# arduino_voltage_monitor_shield.net
KiCad netlist of a schematic drawn in Altium Designer
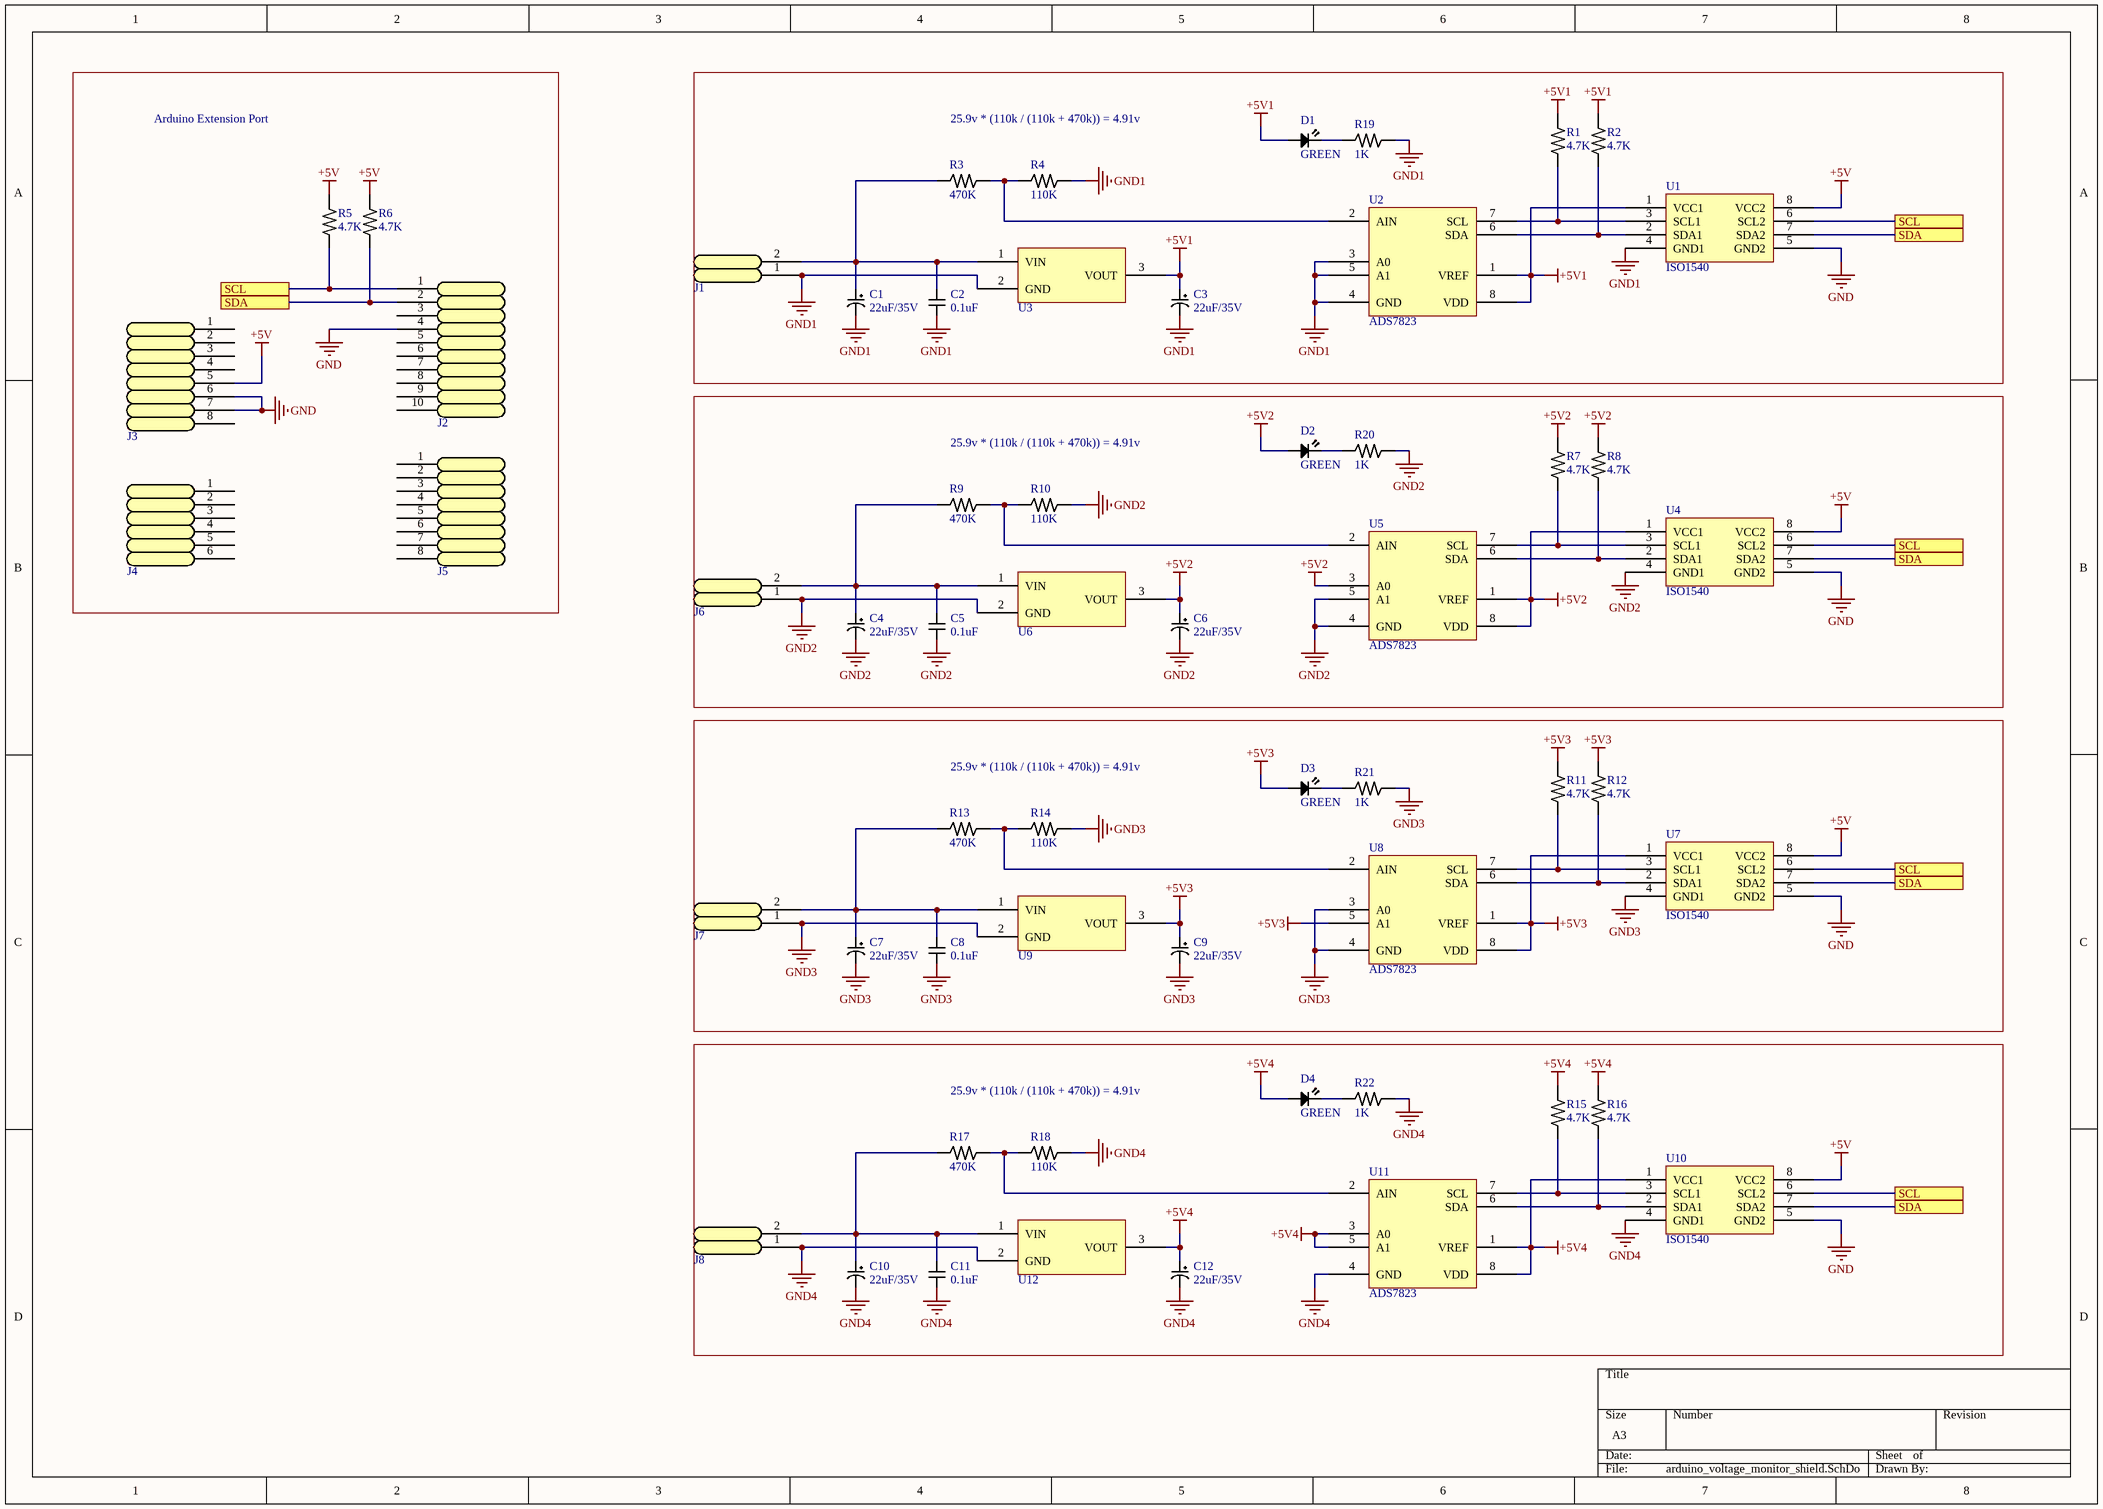
[diagram p0: arduino_voltage_monitor_shield.SchDoc]

(export (version "E")
  (design (tool "Eeschema 10.0.6"))
  (components
    (comp (ref "C1")
      (value "22uF/35V")
      (footprint "ECAP-TANTAL-A")
      (description "Polarized Capacitor")
      (fields (field (name "Comment") "EC"))
      (libsource (lib "arduino_voltage_monitor_shield") (part "EC"))
    )
    (comp (ref "C2")
      (value "0.1uF")
      (footprint "CAP1608L")
      (description "Non-polarized Capacitor")
      (fields (field (name "Comment") "C"))
      (libsource (lib "arduino_voltage_monitor_shield") (part "C"))
    )
    (comp (ref "C3")
      (value "22uF/35V")
      (footprint "ECAP-TANTAL-A")
      (description "Polarized Capacitor")
      (fields (field (name "Comment") "EC"))
      (libsource (lib "arduino_voltage_monitor_shield") (part "EC"))
    )
    (comp (ref "C4")
      (value "22uF/35V")
      (footprint "ECAP-TANTAL-A")
      (description "Polarized Capacitor")
      (fields (field (name "Comment") "EC"))
      (libsource (lib "arduino_voltage_monitor_shield") (part "EC"))
    )
    (comp (ref "C5")
      (value "0.1uF")
      (footprint "CAP1608L")
      (description "Non-polarized Capacitor")
      (fields (field (name "Comment") "C"))
      (libsource (lib "arduino_voltage_monitor_shield") (part "C"))
    )
    (comp (ref "C6")
      (value "22uF/35V")
      (footprint "ECAP-TANTAL-A")
      (description "Polarized Capacitor")
      (fields (field (name "Comment") "EC"))
      (libsource (lib "arduino_voltage_monitor_shield") (part "EC"))
    )
    (comp (ref "C7")
      (value "22uF/35V")
      (footprint "ECAP-TANTAL-A")
      (description "Polarized Capacitor")
      (fields (field (name "Comment") "EC"))
      (libsource (lib "arduino_voltage_monitor_shield") (part "EC"))
    )
    (comp (ref "C8")
      (value "0.1uF")
      (footprint "CAP1608L")
      (description "Non-polarized Capacitor")
      (fields (field (name "Comment") "C"))
      (libsource (lib "arduino_voltage_monitor_shield") (part "C"))
    )
    (comp (ref "C9")
      (value "22uF/35V")
      (footprint "ECAP-TANTAL-A")
      (description "Polarized Capacitor")
      (fields (field (name "Comment") "EC"))
      (libsource (lib "arduino_voltage_monitor_shield") (part "EC"))
    )
    (comp (ref "C10")
      (value "22uF/35V")
      (footprint "ECAP-TANTAL-A")
      (description "Polarized Capacitor")
      (fields (field (name "Comment") "EC"))
      (libsource (lib "arduino_voltage_monitor_shield") (part "EC"))
    )
    (comp (ref "C11")
      (value "0.1uF")
      (footprint "CAP1608L")
      (description "Non-polarized Capacitor")
      (fields (field (name "Comment") "C"))
      (libsource (lib "arduino_voltage_monitor_shield") (part "C"))
    )
    (comp (ref "C12")
      (value "22uF/35V")
      (footprint "ECAP-TANTAL-A")
      (description "Polarized Capacitor")
      (fields (field (name "Comment") "EC"))
      (libsource (lib "arduino_voltage_monitor_shield") (part "EC"))
    )
    (comp (ref "D1")
      (value "GREEN")
      (footprint "LED1608L")
      (description "Typical LED")
      (fields (field (name "Comment") "LED"))
      (libsource (lib "arduino_voltage_monitor_shield") (part "LED"))
    )
    (comp (ref "D2")
      (value "GREEN")
      (footprint "LED1608L")
      (description "Typical LED")
      (fields (field (name "Comment") "LED"))
      (libsource (lib "arduino_voltage_monitor_shield") (part "LED"))
    )
    (comp (ref "D3")
      (value "GREEN")
      (footprint "LED1608L")
      (description "Typical LED")
      (fields (field (name "Comment") "LED"))
      (libsource (lib "arduino_voltage_monitor_shield") (part "LED"))
    )
    (comp (ref "D4")
      (value "GREEN")
      (footprint "LED1608L")
      (description "Typical LED")
      (fields (field (name "Comment") "LED"))
      (libsource (lib "arduino_voltage_monitor_shield") (part "LED"))
    )
    (comp (ref "J1")
      (value "CON2")
      (footprint "DG128-5.0-02P")
      (description "Generic Connector 2 Pin")
      (libsource (lib "arduino_voltage_monitor_shield") (part "CON2"))
    )
    (comp (ref "J2")
      (value "CON10")
      (footprint "PIN-HEADER-2.54-10P")
      (description "Generic Connector 10 Pin")
      (libsource (lib "arduino_voltage_monitor_shield") (part "CON10"))
    )
    (comp (ref "J3")
      (value "CON8")
      (footprint "PIN-HEADER-2.54-8P")
      (description "Generic Connector 8 Pin")
      (libsource (lib "arduino_voltage_monitor_shield") (part "CON8"))
    )
    (comp (ref "J4")
      (value "CON6")
      (footprint "PIN-HEADER-2.54-6P")
      (description "Generic Connector 6 Pin")
      (libsource (lib "arduino_voltage_monitor_shield") (part "CON6"))
    )
    (comp (ref "J5")
      (value "CON8")
      (footprint "PIN-HEADER-2.54-8P")
      (description "Generic Connector 8 Pin")
      (libsource (lib "arduino_voltage_monitor_shield") (part "CON8"))
    )
    (comp (ref "J6")
      (value "CON2")
      (footprint "DG128-5.0-02P")
      (description "Generic Connector 2 Pin")
      (libsource (lib "arduino_voltage_monitor_shield") (part "CON2"))
    )
    (comp (ref "J7")
      (value "CON2")
      (footprint "DG128-5.0-02P")
      (description "Generic Connector 2 Pin")
      (libsource (lib "arduino_voltage_monitor_shield") (part "CON2"))
    )
    (comp (ref "J8")
      (value "CON2")
      (footprint "DG128-5.0-02P")
      (description "Generic Connector 2 Pin")
      (libsource (lib "arduino_voltage_monitor_shield") (part "CON2"))
    )
    (comp (ref "R1")
      (value "4.7K")
      (footprint "RES1608L")
      (description "Resistor")
      (fields (field (name "Comment") "R"))
      (libsource (lib "arduino_voltage_monitor_shield") (part "R"))
    )
    (comp (ref "R2")
      (value "4.7K")
      (footprint "RES1608L")
      (description "Resistor")
      (fields (field (name "Comment") "R"))
      (libsource (lib "arduino_voltage_monitor_shield") (part "R"))
    )
    (comp (ref "R3")
      (value "470K")
      (footprint "RES1608L")
      (description "Resistor")
      (fields (field (name "Comment") "R"))
      (libsource (lib "arduino_voltage_monitor_shield") (part "R"))
    )
    (comp (ref "R4")
      (value "110K")
      (footprint "RES1608L")
      (description "Resistor")
      (fields (field (name "Comment") "R"))
      (libsource (lib "arduino_voltage_monitor_shield") (part "R"))
    )
    (comp (ref "R5")
      (value "4.7K")
      (footprint "RES1608L")
      (description "Resistor")
      (fields (field (name "Comment") "R"))
      (libsource (lib "arduino_voltage_monitor_shield") (part "R"))
    )
    (comp (ref "R6")
      (value "4.7K")
      (footprint "RES1608L")
      (description "Resistor")
      (fields (field (name "Comment") "R"))
      (libsource (lib "arduino_voltage_monitor_shield") (part "R"))
    )
    (comp (ref "R7")
      (value "4.7K")
      (footprint "RES1608L")
      (description "Resistor")
      (fields (field (name "Comment") "R"))
      (libsource (lib "arduino_voltage_monitor_shield") (part "R"))
    )
    (comp (ref "R8")
      (value "4.7K")
      (footprint "RES1608L")
      (description "Resistor")
      (fields (field (name "Comment") "R"))
      (libsource (lib "arduino_voltage_monitor_shield") (part "R"))
    )
    (comp (ref "R9")
      (value "470K")
      (footprint "RES1608L")
      (description "Resistor")
      (fields (field (name "Comment") "R"))
      (libsource (lib "arduino_voltage_monitor_shield") (part "R"))
    )
    (comp (ref "R10")
      (value "110K")
      (footprint "RES1608L")
      (description "Resistor")
      (fields (field (name "Comment") "R"))
      (libsource (lib "arduino_voltage_monitor_shield") (part "R"))
    )
    (comp (ref "R11")
      (value "4.7K")
      (footprint "RES1608L")
      (description "Resistor")
      (fields (field (name "Comment") "R"))
      (libsource (lib "arduino_voltage_monitor_shield") (part "R"))
    )
    (comp (ref "R12")
      (value "4.7K")
      (footprint "RES1608L")
      (description "Resistor")
      (fields (field (name "Comment") "R"))
      (libsource (lib "arduino_voltage_monitor_shield") (part "R"))
    )
    (comp (ref "R13")
      (value "470K")
      (footprint "RES1608L")
      (description "Resistor")
      (fields (field (name "Comment") "R"))
      (libsource (lib "arduino_voltage_monitor_shield") (part "R"))
    )
    (comp (ref "R14")
      (value "110K")
      (footprint "RES1608L")
      (description "Resistor")
      (fields (field (name "Comment") "R"))
      (libsource (lib "arduino_voltage_monitor_shield") (part "R"))
    )
    (comp (ref "R15")
      (value "4.7K")
      (footprint "RES1608L")
      (description "Resistor")
      (fields (field (name "Comment") "R"))
      (libsource (lib "arduino_voltage_monitor_shield") (part "R"))
    )
    (comp (ref "R16")
      (value "4.7K")
      (footprint "RES1608L")
      (description "Resistor")
      (fields (field (name "Comment") "R"))
      (libsource (lib "arduino_voltage_monitor_shield") (part "R"))
    )
    (comp (ref "R17")
      (value "470K")
      (footprint "RES1608L")
      (description "Resistor")
      (fields (field (name "Comment") "R"))
      (libsource (lib "arduino_voltage_monitor_shield") (part "R"))
    )
    (comp (ref "R18")
      (value "110K")
      (footprint "RES1608L")
      (description "Resistor")
      (fields (field (name "Comment") "R"))
      (libsource (lib "arduino_voltage_monitor_shield") (part "R"))
    )
    (comp (ref "R19")
      (value "1K")
      (footprint "RES1608L")
      (description "Resistor")
      (fields (field (name "Comment") "R"))
      (libsource (lib "arduino_voltage_monitor_shield") (part "R"))
    )
    (comp (ref "R20")
      (value "1K")
      (footprint "RES1608L")
      (description "Resistor")
      (fields (field (name "Comment") "R"))
      (libsource (lib "arduino_voltage_monitor_shield") (part "R"))
    )
    (comp (ref "R21")
      (value "1K")
      (footprint "RES1608L")
      (description "Resistor")
      (fields (field (name "Comment") "R"))
      (libsource (lib "arduino_voltage_monitor_shield") (part "R"))
    )
    (comp (ref "R22")
      (value "1K")
      (footprint "RES1608L")
      (description "Resistor")
      (fields (field (name "Comment") "R"))
      (libsource (lib "arduino_voltage_monitor_shield") (part "R"))
    )
    (comp (ref "U1")
      (value "ISO1540")
      (footprint "SOIC-8")
      (description "ISO154x Low-Power Bidirectional I2C Isolators")
      (libsource (lib "arduino_voltage_monitor_shield") (part "ISO1540"))
    )
    (comp (ref "U2")
      (value "ADS7823")
      (footprint "VSSOP-8_DGK")
      (description "12-Bit, Sampling A/D Converter with I2C™ INTERFACE")
      (libsource (lib "arduino_voltage_monitor_shield") (part "ADS7823"))
    )
    (comp (ref "U3")
      (value "R-785.0-0.5")
      (footprint "R-785.0-0.5")
      (description "R-78xx-Series high efficiency switching regulators")
      (libsource (lib "arduino_voltage_monitor_shield") (part "R-785.0-0.5"))
    )
    (comp (ref "U4")
      (value "ISO1540")
      (footprint "SOIC-8")
      (description "ISO154x Low-Power Bidirectional I2C Isolators")
      (libsource (lib "arduino_voltage_monitor_shield") (part "ISO1540"))
    )
    (comp (ref "U5")
      (value "ADS7823")
      (footprint "VSSOP-8_DGK")
      (description "12-Bit, Sampling A/D Converter with I2C™ INTERFACE")
      (libsource (lib "arduino_voltage_monitor_shield") (part "ADS7823"))
    )
    (comp (ref "U6")
      (value "R-785.0-0.5")
      (footprint "R-785.0-0.5")
      (description "R-78xx-Series high efficiency switching regulators")
      (libsource (lib "arduino_voltage_monitor_shield") (part "R-785.0-0.5"))
    )
    (comp (ref "U7")
      (value "ISO1540")
      (footprint "SOIC-8")
      (description "ISO154x Low-Power Bidirectional I2C Isolators")
      (libsource (lib "arduino_voltage_monitor_shield") (part "ISO1540"))
    )
    (comp (ref "U8")
      (value "ADS7823")
      (footprint "VSSOP-8_DGK")
      (description "12-Bit, Sampling A/D Converter with I2C™ INTERFACE")
      (libsource (lib "arduino_voltage_monitor_shield") (part "ADS7823"))
    )
    (comp (ref "U9")
      (value "R-785.0-0.5")
      (footprint "R-785.0-0.5")
      (description "R-78xx-Series high efficiency switching regulators")
      (libsource (lib "arduino_voltage_monitor_shield") (part "R-785.0-0.5"))
    )
    (comp (ref "U10")
      (value "ISO1540")
      (footprint "SOIC-8")
      (description "ISO154x Low-Power Bidirectional I2C Isolators")
      (libsource (lib "arduino_voltage_monitor_shield") (part "ISO1540"))
    )
    (comp (ref "U11")
      (value "ADS7823")
      (footprint "VSSOP-8_DGK")
      (description "12-Bit, Sampling A/D Converter with I2C™ INTERFACE")
      (libsource (lib "arduino_voltage_monitor_shield") (part "ADS7823"))
    )
    (comp (ref "U12")
      (value "R-785.0-0.5")
      (footprint "R-785.0-0.5")
      (description "R-78xx-Series high efficiency switching regulators")
      (libsource (lib "arduino_voltage_monitor_shield") (part "R-785.0-0.5"))
    )
  )
  (nets
    (net (code "1") (name "+5V") (class "Default")
      (node (ref "J3") (pin "5") (pinfunction "5_5") (pintype "passive"))
      (node (ref "R5") (pin "2") (pinfunction "2_2") (pintype "passive"))
      (node (ref "R6") (pin "2") (pinfunction "2_2") (pintype "passive"))
      (node (ref "U1") (pin "8") (pinfunction "VCC2_8") (pintype "passive"))
      (node (ref "U10") (pin "8") (pinfunction "VCC2_8") (pintype "passive"))
      (node (ref "U4") (pin "8") (pinfunction "VCC2_8") (pintype "passive"))
      (node (ref "U7") (pin "8") (pinfunction "VCC2_8") (pintype "passive"))
    )
    (net (code "2") (name "+5V1") (class "Default")
      (node (ref "C3") (pin "1") (pinfunction "1_1") (pintype "passive"))
      (node (ref "D1") (pin "2") (pinfunction "2_2") (pintype "passive"))
      (node (ref "R1") (pin "2") (pinfunction "2_2") (pintype "passive"))
      (node (ref "R2") (pin "2") (pinfunction "2_2") (pintype "passive"))
      (node (ref "U1") (pin "1") (pinfunction "VCC1_1") (pintype "passive"))
      (node (ref "U2") (pin "1") (pinfunction "VREF_1") (pintype "passive"))
      (node (ref "U2") (pin "8") (pinfunction "VDD_8") (pintype "passive"))
      (node (ref "U3") (pin "3") (pinfunction "VOUT_3") (pintype "passive"))
    )
    (net (code "3") (name "+5V2") (class "Default")
      (node (ref "C6") (pin "1") (pinfunction "1_1") (pintype "passive"))
      (node (ref "D2") (pin "2") (pinfunction "2_2") (pintype "passive"))
      (node (ref "R7") (pin "2") (pinfunction "2_2") (pintype "passive"))
      (node (ref "R8") (pin "2") (pinfunction "2_2") (pintype "passive"))
      (node (ref "U4") (pin "1") (pinfunction "VCC1_1") (pintype "passive"))
      (node (ref "U5") (pin "1") (pinfunction "VREF_1") (pintype "passive"))
      (node (ref "U5") (pin "3") (pinfunction "A0_3") (pintype "passive"))
      (node (ref "U5") (pin "8") (pinfunction "VDD_8") (pintype "passive"))
      (node (ref "U6") (pin "3") (pinfunction "VOUT_3") (pintype "passive"))
    )
    (net (code "4") (name "+5V3") (class "Default")
      (node (ref "C9") (pin "1") (pinfunction "1_1") (pintype "passive"))
      (node (ref "D3") (pin "2") (pinfunction "2_2") (pintype "passive"))
      (node (ref "R11") (pin "2") (pinfunction "2_2") (pintype "passive"))
      (node (ref "R12") (pin "2") (pinfunction "2_2") (pintype "passive"))
      (node (ref "U7") (pin "1") (pinfunction "VCC1_1") (pintype "passive"))
      (node (ref "U8") (pin "1") (pinfunction "VREF_1") (pintype "passive"))
      (node (ref "U8") (pin "5") (pinfunction "A1_5") (pintype "passive"))
      (node (ref "U8") (pin "8") (pinfunction "VDD_8") (pintype "passive"))
      (node (ref "U9") (pin "3") (pinfunction "VOUT_3") (pintype "passive"))
    )
    (net (code "5") (name "+5V4") (class "Default")
      (node (ref "C12") (pin "1") (pinfunction "1_1") (pintype "passive"))
      (node (ref "D4") (pin "2") (pinfunction "2_2") (pintype "passive"))
      (node (ref "R15") (pin "2") (pinfunction "2_2") (pintype "passive"))
      (node (ref "R16") (pin "2") (pinfunction "2_2") (pintype "passive"))
      (node (ref "U10") (pin "1") (pinfunction "VCC1_1") (pintype "passive"))
      (node (ref "U11") (pin "1") (pinfunction "VREF_1") (pintype "passive"))
      (node (ref "U11") (pin "3") (pinfunction "A0_3") (pintype "passive"))
      (node (ref "U11") (pin "5") (pinfunction "A1_5") (pintype "passive"))
      (node (ref "U11") (pin "8") (pinfunction "VDD_8") (pintype "passive"))
      (node (ref "U12") (pin "3") (pinfunction "VOUT_3") (pintype "passive"))
    )
    (net (code "6") (name "/SCL") (class "Default")
      (node (ref "J2") (pin "1") (pinfunction "1_1") (pintype "passive"))
      (node (ref "R5") (pin "1") (pinfunction "1_1") (pintype "passive"))
      (node (ref "U1") (pin "6") (pinfunction "SCL2_6") (pintype "passive"))
      (node (ref "U10") (pin "6") (pinfunction "SCL2_6") (pintype "passive"))
      (node (ref "U4") (pin "6") (pinfunction "SCL2_6") (pintype "passive"))
      (node (ref "U7") (pin "6") (pinfunction "SCL2_6") (pintype "passive"))
    )
    (net (code "7") (name "/SDA") (class "Default")
      (node (ref "J2") (pin "2") (pinfunction "2_2") (pintype "passive"))
      (node (ref "R6") (pin "1") (pinfunction "1_1") (pintype "passive"))
      (node (ref "U1") (pin "7") (pinfunction "SDA2_7") (pintype "passive"))
      (node (ref "U10") (pin "7") (pinfunction "SDA2_7") (pintype "passive"))
      (node (ref "U4") (pin "7") (pinfunction "SDA2_7") (pintype "passive"))
      (node (ref "U7") (pin "7") (pinfunction "SDA2_7") (pintype "passive"))
    )
    (net (code "8") (name "GND") (class "Default")
      (node (ref "J2") (pin "4") (pinfunction "4_4") (pintype "passive"))
      (node (ref "J3") (pin "6") (pinfunction "6_6") (pintype "passive"))
      (node (ref "J3") (pin "7") (pinfunction "7_7") (pintype "passive"))
      (node (ref "U1") (pin "5") (pinfunction "GND2_5") (pintype "passive"))
      (node (ref "U10") (pin "5") (pinfunction "GND2_5") (pintype "passive"))
      (node (ref "U4") (pin "5") (pinfunction "GND2_5") (pintype "passive"))
      (node (ref "U7") (pin "5") (pinfunction "GND2_5") (pintype "passive"))
    )
    (net (code "9") (name "GND1") (class "Default")
      (node (ref "C1") (pin "2") (pinfunction "2_2") (pintype "passive"))
      (node (ref "C2") (pin "1") (pinfunction "1_1") (pintype "passive"))
      (node (ref "C3") (pin "2") (pinfunction "2_2") (pintype "passive"))
      (node (ref "J1") (pin "1") (pinfunction "1_1") (pintype "passive"))
      (node (ref "R19") (pin "2") (pinfunction "2_2") (pintype "passive"))
      (node (ref "R4") (pin "2") (pinfunction "2_2") (pintype "passive"))
      (node (ref "U1") (pin "4") (pinfunction "GND1_4") (pintype "passive"))
      (node (ref "U2") (pin "3") (pinfunction "A0_3") (pintype "passive"))
      (node (ref "U2") (pin "4") (pinfunction "GND_4") (pintype "passive"))
      (node (ref "U2") (pin "5") (pinfunction "A1_5") (pintype "passive"))
      (node (ref "U3") (pin "2") (pinfunction "GND_2") (pintype "passive"))
    )
    (net (code "10") (name "GND2") (class "Default")
      (node (ref "C4") (pin "2") (pinfunction "2_2") (pintype "passive"))
      (node (ref "C5") (pin "1") (pinfunction "1_1") (pintype "passive"))
      (node (ref "C6") (pin "2") (pinfunction "2_2") (pintype "passive"))
      (node (ref "J6") (pin "1") (pinfunction "1_1") (pintype "passive"))
      (node (ref "R10") (pin "2") (pinfunction "2_2") (pintype "passive"))
      (node (ref "R20") (pin "2") (pinfunction "2_2") (pintype "passive"))
      (node (ref "U4") (pin "4") (pinfunction "GND1_4") (pintype "passive"))
      (node (ref "U5") (pin "4") (pinfunction "GND_4") (pintype "passive"))
      (node (ref "U5") (pin "5") (pinfunction "A1_5") (pintype "passive"))
      (node (ref "U6") (pin "2") (pinfunction "GND_2") (pintype "passive"))
    )
    (net (code "11") (name "GND3") (class "Default")
      (node (ref "C7") (pin "2") (pinfunction "2_2") (pintype "passive"))
      (node (ref "C8") (pin "1") (pinfunction "1_1") (pintype "passive"))
      (node (ref "C9") (pin "2") (pinfunction "2_2") (pintype "passive"))
      (node (ref "J7") (pin "1") (pinfunction "1_1") (pintype "passive"))
      (node (ref "R14") (pin "2") (pinfunction "2_2") (pintype "passive"))
      (node (ref "R21") (pin "2") (pinfunction "2_2") (pintype "passive"))
      (node (ref "U7") (pin "4") (pinfunction "GND1_4") (pintype "passive"))
      (node (ref "U8") (pin "3") (pinfunction "A0_3") (pintype "passive"))
      (node (ref "U8") (pin "4") (pinfunction "GND_4") (pintype "passive"))
      (node (ref "U9") (pin "2") (pinfunction "GND_2") (pintype "passive"))
    )
    (net (code "12") (name "GND4") (class "Default")
      (node (ref "C10") (pin "2") (pinfunction "2_2") (pintype "passive"))
      (node (ref "C11") (pin "1") (pinfunction "1_1") (pintype "passive"))
      (node (ref "C12") (pin "2") (pinfunction "2_2") (pintype "passive"))
      (node (ref "J8") (pin "1") (pinfunction "1_1") (pintype "passive"))
      (node (ref "R18") (pin "2") (pinfunction "2_2") (pintype "passive"))
      (node (ref "R22") (pin "2") (pinfunction "2_2") (pintype "passive"))
      (node (ref "U10") (pin "4") (pinfunction "GND1_4") (pintype "passive"))
      (node (ref "U11") (pin "4") (pinfunction "GND_4") (pintype "passive"))
      (node (ref "U12") (pin "2") (pinfunction "GND_2") (pintype "passive"))
    )
    (net (code "13") (name "Net-(D1-Pad1)") (class "Default")
      (node (ref "D1") (pin "1") (pinfunction "1_1") (pintype "passive"))
      (node (ref "R19") (pin "1") (pinfunction "1_1") (pintype "passive"))
    )
    (net (code "14") (name "Net-(D2-Pad1)") (class "Default")
      (node (ref "D2") (pin "1") (pinfunction "1_1") (pintype "passive"))
      (node (ref "R20") (pin "1") (pinfunction "1_1") (pintype "passive"))
    )
    (net (code "15") (name "Net-(D3-Pad1)") (class "Default")
      (node (ref "D3") (pin "1") (pinfunction "1_1") (pintype "passive"))
      (node (ref "R21") (pin "1") (pinfunction "1_1") (pintype "passive"))
    )
    (net (code "16") (name "Net-(D4-Pad1)") (class "Default")
      (node (ref "D4") (pin "1") (pinfunction "1_1") (pintype "passive"))
      (node (ref "R22") (pin "1") (pinfunction "1_1") (pintype "passive"))
    )
    (net (code "17") (name "Net-(U1-SCL1)") (class "Default")
      (node (ref "R1") (pin "1") (pinfunction "1_1") (pintype "passive"))
      (node (ref "U1") (pin "3") (pinfunction "SCL1_3") (pintype "passive"))
      (node (ref "U2") (pin "7") (pinfunction "SCL_7") (pintype "passive"))
    )
    (net (code "18") (name "Net-(U1-SDA1)") (class "Default")
      (node (ref "R2") (pin "1") (pinfunction "1_1") (pintype "passive"))
      (node (ref "U1") (pin "2") (pinfunction "SDA1_2") (pintype "passive"))
      (node (ref "U2") (pin "6") (pinfunction "SDA_6") (pintype "passive"))
    )
    (net (code "19") (name "Net-(U2-AIN)") (class "Default")
      (node (ref "R3") (pin "2") (pinfunction "2_2") (pintype "passive"))
      (node (ref "R4") (pin "1") (pinfunction "1_1") (pintype "passive"))
      (node (ref "U2") (pin "2") (pinfunction "AIN_2") (pintype "passive"))
    )
    (net (code "20") (name "Net-(U3-VIN)") (class "Default")
      (node (ref "C1") (pin "1") (pinfunction "1_1") (pintype "passive"))
      (node (ref "C2") (pin "2") (pinfunction "2_2") (pintype "passive"))
      (node (ref "J1") (pin "2") (pinfunction "2_2") (pintype "passive"))
      (node (ref "R3") (pin "1") (pinfunction "1_1") (pintype "passive"))
      (node (ref "U3") (pin "1") (pinfunction "VIN_1") (pintype "passive"))
    )
    (net (code "21") (name "Net-(U4-SCL1)") (class "Default")
      (node (ref "R7") (pin "1") (pinfunction "1_1") (pintype "passive"))
      (node (ref "U4") (pin "3") (pinfunction "SCL1_3") (pintype "passive"))
      (node (ref "U5") (pin "7") (pinfunction "SCL_7") (pintype "passive"))
    )
    (net (code "22") (name "Net-(U4-SDA1)") (class "Default")
      (node (ref "R8") (pin "1") (pinfunction "1_1") (pintype "passive"))
      (node (ref "U4") (pin "2") (pinfunction "SDA1_2") (pintype "passive"))
      (node (ref "U5") (pin "6") (pinfunction "SDA_6") (pintype "passive"))
    )
    (net (code "23") (name "Net-(U5-AIN)") (class "Default")
      (node (ref "R10") (pin "1") (pinfunction "1_1") (pintype "passive"))
      (node (ref "R9") (pin "2") (pinfunction "2_2") (pintype "passive"))
      (node (ref "U5") (pin "2") (pinfunction "AIN_2") (pintype "passive"))
    )
    (net (code "24") (name "Net-(U6-VIN)") (class "Default")
      (node (ref "C4") (pin "1") (pinfunction "1_1") (pintype "passive"))
      (node (ref "C5") (pin "2") (pinfunction "2_2") (pintype "passive"))
      (node (ref "J6") (pin "2") (pinfunction "2_2") (pintype "passive"))
      (node (ref "R9") (pin "1") (pinfunction "1_1") (pintype "passive"))
      (node (ref "U6") (pin "1") (pinfunction "VIN_1") (pintype "passive"))
    )
    (net (code "25") (name "Net-(U7-SCL1)") (class "Default")
      (node (ref "R11") (pin "1") (pinfunction "1_1") (pintype "passive"))
      (node (ref "U7") (pin "3") (pinfunction "SCL1_3") (pintype "passive"))
      (node (ref "U8") (pin "7") (pinfunction "SCL_7") (pintype "passive"))
    )
    (net (code "26") (name "Net-(U7-SDA1)") (class "Default")
      (node (ref "R12") (pin "1") (pinfunction "1_1") (pintype "passive"))
      (node (ref "U7") (pin "2") (pinfunction "SDA1_2") (pintype "passive"))
      (node (ref "U8") (pin "6") (pinfunction "SDA_6") (pintype "passive"))
    )
    (net (code "27") (name "Net-(U8-AIN)") (class "Default")
      (node (ref "R13") (pin "2") (pinfunction "2_2") (pintype "passive"))
      (node (ref "R14") (pin "1") (pinfunction "1_1") (pintype "passive"))
      (node (ref "U8") (pin "2") (pinfunction "AIN_2") (pintype "passive"))
    )
    (net (code "28") (name "Net-(U9-VIN)") (class "Default")
      (node (ref "C7") (pin "1") (pinfunction "1_1") (pintype "passive"))
      (node (ref "C8") (pin "2") (pinfunction "2_2") (pintype "passive"))
      (node (ref "J7") (pin "2") (pinfunction "2_2") (pintype "passive"))
      (node (ref "R13") (pin "1") (pinfunction "1_1") (pintype "passive"))
      (node (ref "U9") (pin "1") (pinfunction "VIN_1") (pintype "passive"))
    )
    (net (code "29") (name "Net-(U10-SCL1)") (class "Default")
      (node (ref "R15") (pin "1") (pinfunction "1_1") (pintype "passive"))
      (node (ref "U10") (pin "3") (pinfunction "SCL1_3") (pintype "passive"))
      (node (ref "U11") (pin "7") (pinfunction "SCL_7") (pintype "passive"))
    )
    (net (code "30") (name "Net-(U10-SDA1)") (class "Default")
      (node (ref "R16") (pin "1") (pinfunction "1_1") (pintype "passive"))
      (node (ref "U10") (pin "2") (pinfunction "SDA1_2") (pintype "passive"))
      (node (ref "U11") (pin "6") (pinfunction "SDA_6") (pintype "passive"))
    )
    (net (code "31") (name "Net-(U11-AIN)") (class "Default")
      (node (ref "R17") (pin "2") (pinfunction "2_2") (pintype "passive"))
      (node (ref "R18") (pin "1") (pinfunction "1_1") (pintype "passive"))
      (node (ref "U11") (pin "2") (pinfunction "AIN_2") (pintype "passive"))
    )
    (net (code "32") (name "Net-(U12-VIN)") (class "Default")
      (node (ref "C10") (pin "1") (pinfunction "1_1") (pintype "passive"))
      (node (ref "C11") (pin "2") (pinfunction "2_2") (pintype "passive"))
      (node (ref "J8") (pin "2") (pinfunction "2_2") (pintype "passive"))
      (node (ref "R17") (pin "1") (pinfunction "1_1") (pintype "passive"))
      (node (ref "U12") (pin "1") (pinfunction "VIN_1") (pintype "passive"))
    )
    (net (code "33") (name "unconnected-(J2-Pad3)") (class "Default")
      (node (ref "J2") (pin "3") (pinfunction "3_3") (pintype "passive"))
    )
    (net (code "34") (name "unconnected-(J2-Pad5)") (class "Default")
      (node (ref "J2") (pin "5") (pinfunction "5_5") (pintype "passive"))
    )
    (net (code "35") (name "unconnected-(J2-Pad6)") (class "Default")
      (node (ref "J2") (pin "6") (pinfunction "6_6") (pintype "passive"))
    )
    (net (code "36") (name "unconnected-(J2-Pad7)") (class "Default")
      (node (ref "J2") (pin "7") (pinfunction "7_7") (pintype "passive"))
    )
    (net (code "37") (name "unconnected-(J2-Pad8)") (class "Default")
      (node (ref "J2") (pin "8") (pinfunction "8_8") (pintype "passive"))
    )
    (net (code "38") (name "unconnected-(J2-Pad9)") (class "Default")
      (node (ref "J2") (pin "9") (pinfunction "9_9") (pintype "passive"))
    )
    (net (code "39") (name "unconnected-(J2-Pad10)") (class "Default")
      (node (ref "J2") (pin "10") (pinfunction "10_10") (pintype "passive"))
    )
    (net (code "40") (name "unconnected-(J3-Pad1)") (class "Default")
      (node (ref "J3") (pin "1") (pinfunction "1_1") (pintype "passive"))
    )
    (net (code "41") (name "unconnected-(J3-Pad2)") (class "Default")
      (node (ref "J3") (pin "2") (pinfunction "2_2") (pintype "passive"))
    )
    (net (code "42") (name "unconnected-(J3-Pad3)") (class "Default")
      (node (ref "J3") (pin "3") (pinfunction "3_3") (pintype "passive"))
    )
    (net (code "43") (name "unconnected-(J3-Pad4)") (class "Default")
      (node (ref "J3") (pin "4") (pinfunction "4_4") (pintype "passive"))
    )
    (net (code "44") (name "unconnected-(J3-Pad8)") (class "Default")
      (node (ref "J3") (pin "8") (pinfunction "8_8") (pintype "passive"))
    )
    (net (code "45") (name "unconnected-(J4-Pad1)") (class "Default")
      (node (ref "J4") (pin "1") (pinfunction "1_1") (pintype "passive"))
    )
    (net (code "46") (name "unconnected-(J4-Pad2)") (class "Default")
      (node (ref "J4") (pin "2") (pinfunction "2_2") (pintype "passive"))
    )
    (net (code "47") (name "unconnected-(J4-Pad3)") (class "Default")
      (node (ref "J4") (pin "3") (pinfunction "3_3") (pintype "passive"))
    )
    (net (code "48") (name "unconnected-(J4-Pad4)") (class "Default")
      (node (ref "J4") (pin "4") (pinfunction "4_4") (pintype "passive"))
    )
    (net (code "49") (name "unconnected-(J4-Pad5)") (class "Default")
      (node (ref "J4") (pin "5") (pinfunction "5_5") (pintype "passive"))
    )
    (net (code "50") (name "unconnected-(J4-Pad6)") (class "Default")
      (node (ref "J4") (pin "6") (pinfunction "6_6") (pintype "passive"))
    )
    (net (code "51") (name "unconnected-(J5-Pad1)") (class "Default")
      (node (ref "J5") (pin "1") (pinfunction "1_1") (pintype "passive"))
    )
    (net (code "52") (name "unconnected-(J5-Pad2)") (class "Default")
      (node (ref "J5") (pin "2") (pinfunction "2_2") (pintype "passive"))
    )
    (net (code "53") (name "unconnected-(J5-Pad3)") (class "Default")
      (node (ref "J5") (pin "3") (pinfunction "3_3") (pintype "passive"))
    )
    (net (code "54") (name "unconnected-(J5-Pad4)") (class "Default")
      (node (ref "J5") (pin "4") (pinfunction "4_4") (pintype "passive"))
    )
    (net (code "55") (name "unconnected-(J5-Pad5)") (class "Default")
      (node (ref "J5") (pin "5") (pinfunction "5_5") (pintype "passive"))
    )
    (net (code "56") (name "unconnected-(J5-Pad6)") (class "Default")
      (node (ref "J5") (pin "6") (pinfunction "6_6") (pintype "passive"))
    )
    (net (code "57") (name "unconnected-(J5-Pad7)") (class "Default")
      (node (ref "J5") (pin "7") (pinfunction "7_7") (pintype "passive"))
    )
    (net (code "58") (name "unconnected-(J5-Pad8)") (class "Default")
      (node (ref "J5") (pin "8") (pinfunction "8_8") (pintype "passive"))
    )
  )
)
